# 2364-27c128_adapter.net
KiCad netlist of a schematic drawn in EAGLE
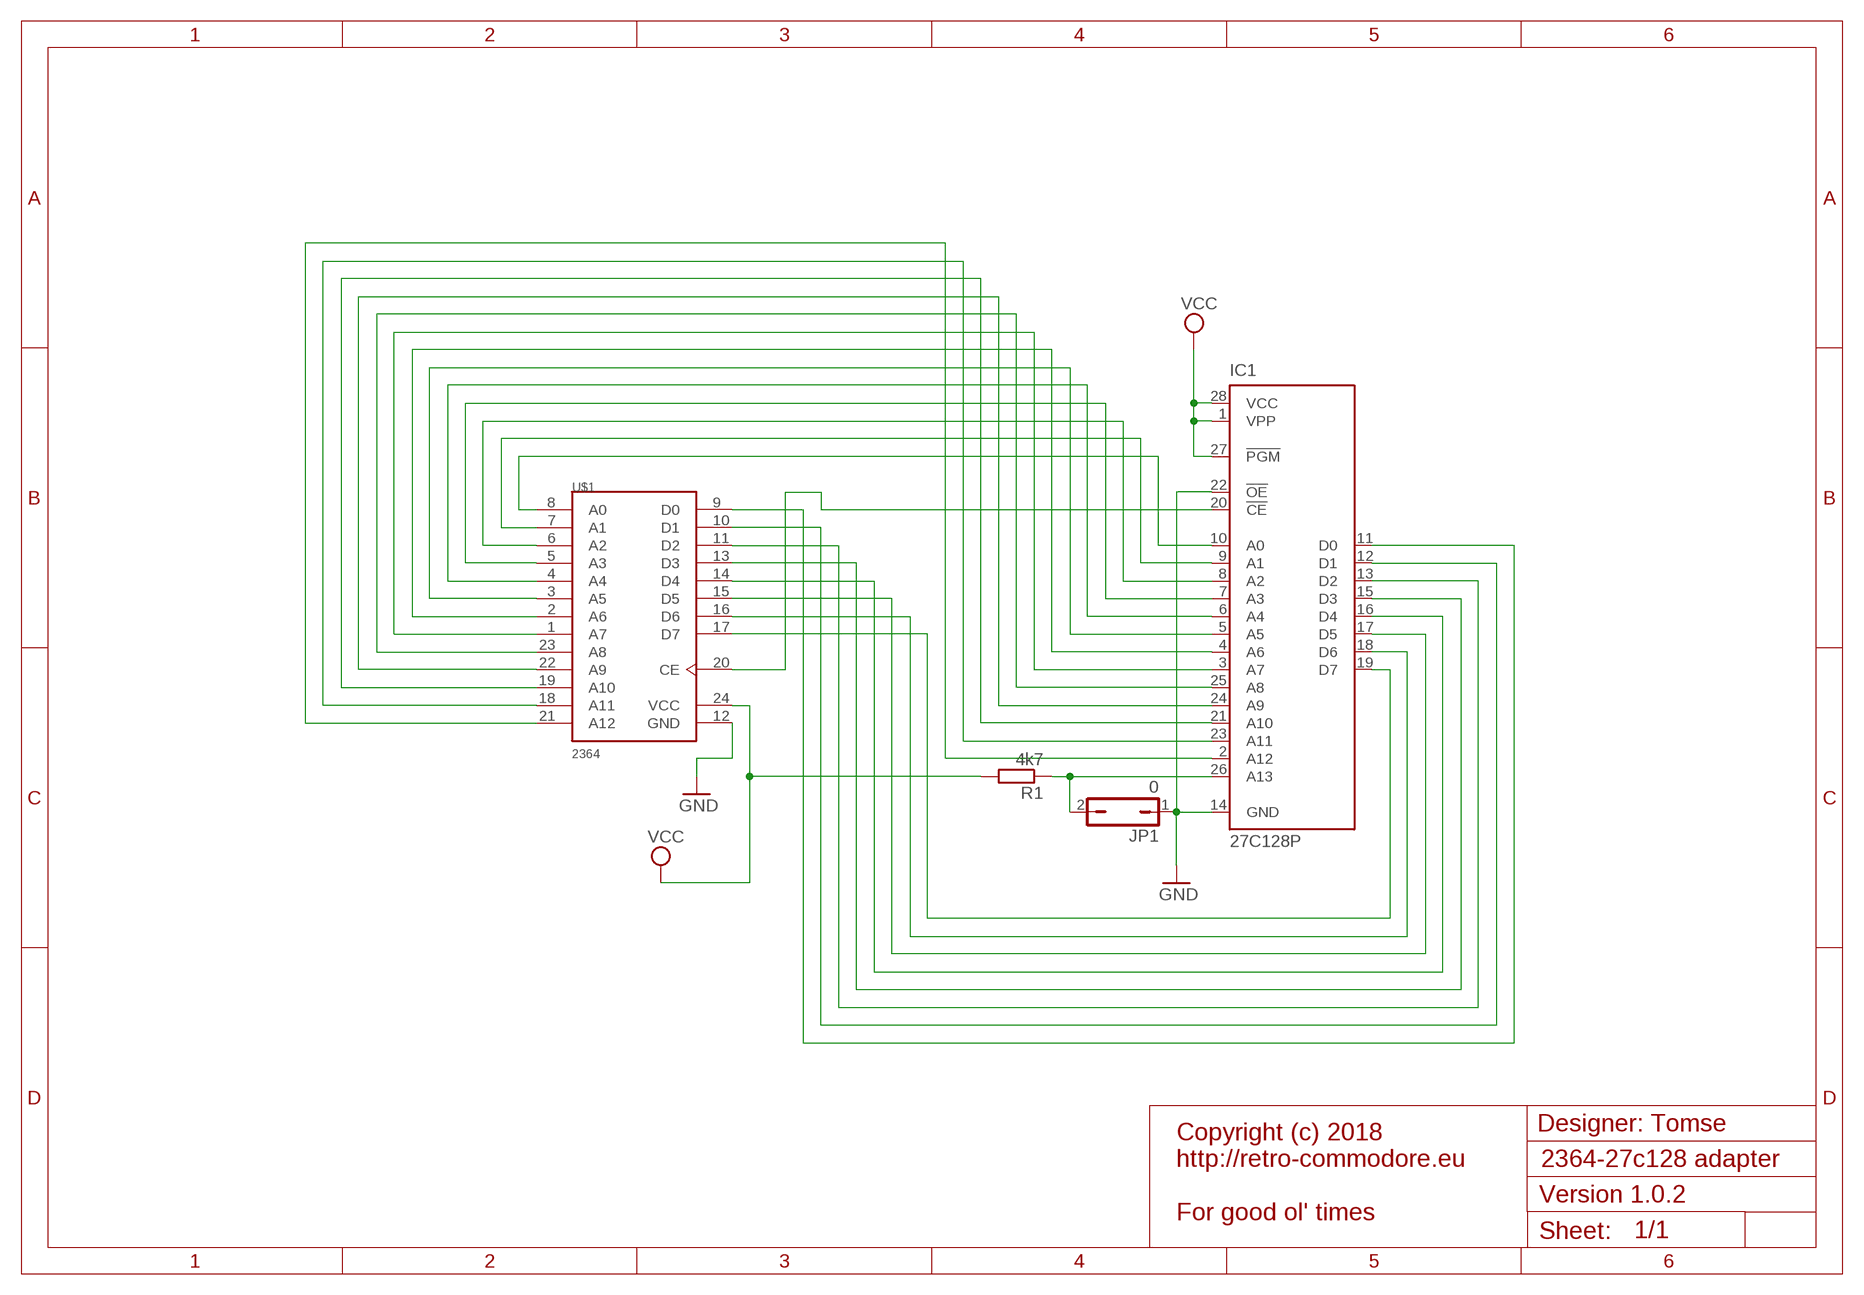
[diagram p0: schematic, sheet 1]

(export (version "E")
  (design (tool "Eeschema 10.0.6"))
  (components
    (comp (ref "IC1")
      (value "27C128P")
      (footprint "eagle-import:DIL28-6")
      (libsource (lib "eagle-import") (part "27128PC"))
    )
    (comp (ref "JP1")
      (value "0")
      (footprint "eagle-import:JP1")
      (libsource (lib "eagle-import") (part "JP1Q"))
    )
    (comp (ref "R1")
      (value "4k7")
      (footprint "eagle-import:0207_12")
      (libsource (lib "eagle-import") (part "R-EU_0207/12"))
    )
    (comp (ref "U$1")
      (value "2364")
      (footprint "eagle-import:DIP24")
      (libsource (lib "eagle-import") (part "2364"))
    )
  )
  (nets
    (net (code "1") (name "GND") (class "Default")
      (node (ref "IC1") (pin "14") (pinfunction "GND_14") (pintype "power_in"))
      (node (ref "IC1") (pin "22") (pinfunction "~{OE}_22") (pintype "input"))
      (node (ref "JP1") (pin "1") (pinfunction "1_1") (pintype "passive"))
      (node (ref "U$1") (pin "12") (pinfunction "GND_12") (pintype "power_in"))
    )
    (net (code "2") (name "Net-(IC1-A0)") (class "Default")
      (node (ref "IC1") (pin "10") (pinfunction "A0_10") (pintype "input"))
      (node (ref "U$1") (pin "8") (pinfunction "A0_8") (pintype "bidirectional"))
    )
    (net (code "3") (name "Net-(IC1-A1)") (class "Default")
      (node (ref "IC1") (pin "9") (pinfunction "A1_9") (pintype "input"))
      (node (ref "U$1") (pin "7") (pinfunction "A1_7") (pintype "bidirectional"))
    )
    (net (code "4") (name "Net-(IC1-A2)") (class "Default")
      (node (ref "IC1") (pin "8") (pinfunction "A2_8") (pintype "input"))
      (node (ref "U$1") (pin "6") (pinfunction "A2_6") (pintype "bidirectional"))
    )
    (net (code "5") (name "Net-(IC1-A3)") (class "Default")
      (node (ref "IC1") (pin "7") (pinfunction "A3_7") (pintype "input"))
      (node (ref "U$1") (pin "5") (pinfunction "A3_5") (pintype "bidirectional"))
    )
    (net (code "6") (name "Net-(IC1-A4)") (class "Default")
      (node (ref "IC1") (pin "6") (pinfunction "A4_6") (pintype "input"))
      (node (ref "U$1") (pin "4") (pinfunction "A4_4") (pintype "bidirectional"))
    )
    (net (code "7") (name "Net-(IC1-A5)") (class "Default")
      (node (ref "IC1") (pin "5") (pinfunction "A5_5") (pintype "input"))
      (node (ref "U$1") (pin "3") (pinfunction "A5_3") (pintype "bidirectional"))
    )
    (net (code "8") (name "Net-(IC1-A6)") (class "Default")
      (node (ref "IC1") (pin "4") (pinfunction "A6_4") (pintype "input"))
      (node (ref "U$1") (pin "2") (pinfunction "A6_2") (pintype "bidirectional"))
    )
    (net (code "9") (name "Net-(IC1-A7)") (class "Default")
      (node (ref "IC1") (pin "3") (pinfunction "A7_3") (pintype "input"))
      (node (ref "U$1") (pin "1") (pinfunction "A7_1") (pintype "bidirectional"))
    )
    (net (code "10") (name "Net-(IC1-A8)") (class "Default")
      (node (ref "IC1") (pin "25") (pinfunction "A8_25") (pintype "input"))
      (node (ref "U$1") (pin "23") (pinfunction "A8_23") (pintype "bidirectional"))
    )
    (net (code "11") (name "Net-(IC1-A9)") (class "Default")
      (node (ref "IC1") (pin "24") (pinfunction "A9_24") (pintype "input"))
      (node (ref "U$1") (pin "22") (pinfunction "A9_22") (pintype "bidirectional"))
    )
    (net (code "12") (name "Net-(IC1-A10)") (class "Default")
      (node (ref "IC1") (pin "21") (pinfunction "A10_21") (pintype "input"))
      (node (ref "U$1") (pin "19") (pinfunction "A10_19") (pintype "bidirectional"))
    )
    (net (code "13") (name "Net-(IC1-A11)") (class "Default")
      (node (ref "IC1") (pin "23") (pinfunction "A11_23") (pintype "input"))
      (node (ref "U$1") (pin "18") (pinfunction "A11_18") (pintype "bidirectional"))
    )
    (net (code "14") (name "Net-(IC1-A12)") (class "Default")
      (node (ref "IC1") (pin "2") (pinfunction "A12_2") (pintype "input"))
      (node (ref "U$1") (pin "21") (pinfunction "A12_21") (pintype "bidirectional"))
    )
    (net (code "15") (name "Net-(IC1-A13)") (class "Default")
      (node (ref "IC1") (pin "26") (pinfunction "A13_26") (pintype "input"))
      (node (ref "JP1") (pin "2") (pinfunction "2_2") (pintype "passive"))
      (node (ref "R1") (pin "1") (pinfunction "1_1") (pintype "passive"))
    )
    (net (code "16") (name "Net-(IC1-D0)") (class "Default")
      (node (ref "IC1") (pin "11") (pinfunction "D0_11") (pintype "tri_state"))
      (node (ref "U$1") (pin "9") (pinfunction "D0_9") (pintype "bidirectional"))
    )
    (net (code "17") (name "Net-(IC1-D1)") (class "Default")
      (node (ref "IC1") (pin "12") (pinfunction "D1_12") (pintype "tri_state"))
      (node (ref "U$1") (pin "10") (pinfunction "D1_10") (pintype "bidirectional"))
    )
    (net (code "18") (name "Net-(IC1-D2)") (class "Default")
      (node (ref "IC1") (pin "13") (pinfunction "D2_13") (pintype "tri_state"))
      (node (ref "U$1") (pin "11") (pinfunction "D2_11") (pintype "bidirectional"))
    )
    (net (code "19") (name "Net-(IC1-D3)") (class "Default")
      (node (ref "IC1") (pin "15") (pinfunction "D3_15") (pintype "tri_state"))
      (node (ref "U$1") (pin "13") (pinfunction "D3_13") (pintype "bidirectional"))
    )
    (net (code "20") (name "Net-(IC1-D4)") (class "Default")
      (node (ref "IC1") (pin "16") (pinfunction "D4_16") (pintype "tri_state"))
      (node (ref "U$1") (pin "14") (pinfunction "D4_14") (pintype "bidirectional"))
    )
    (net (code "21") (name "Net-(IC1-D5)") (class "Default")
      (node (ref "IC1") (pin "17") (pinfunction "D5_17") (pintype "tri_state"))
      (node (ref "U$1") (pin "15") (pinfunction "D5_15") (pintype "bidirectional"))
    )
    (net (code "22") (name "Net-(IC1-D6)") (class "Default")
      (node (ref "IC1") (pin "18") (pinfunction "D6_18") (pintype "tri_state"))
      (node (ref "U$1") (pin "16") (pinfunction "D6_16") (pintype "bidirectional"))
    )
    (net (code "23") (name "Net-(IC1-D7)") (class "Default")
      (node (ref "IC1") (pin "19") (pinfunction "D7_19") (pintype "tri_state"))
      (node (ref "U$1") (pin "17") (pinfunction "D7_17") (pintype "bidirectional"))
    )
    (net (code "24") (name "Net-(IC1-~{CE})") (class "Default")
      (node (ref "IC1") (pin "20") (pinfunction "~{CE}_20") (pintype "input"))
      (node (ref "U$1") (pin "20") (pinfunction "CE_20") (pintype "input"))
    )
    (net (code "25") (name "VCC") (class "Default")
      (node (ref "IC1") (pin "1") (pinfunction "VPP_1") (pintype "input"))
      (node (ref "IC1") (pin "27") (pinfunction "~{PGM}_27") (pintype "passive"))
      (node (ref "IC1") (pin "28") (pinfunction "VCC_28") (pintype "power_in"))
      (node (ref "R1") (pin "2") (pinfunction "2_2") (pintype "passive"))
      (node (ref "U$1") (pin "24") (pinfunction "VCC_24") (pintype "power_in"))
    )
  )
)
